# JETSON_V2.net
KiCad netlist of a schematic drawn in Altium Designer
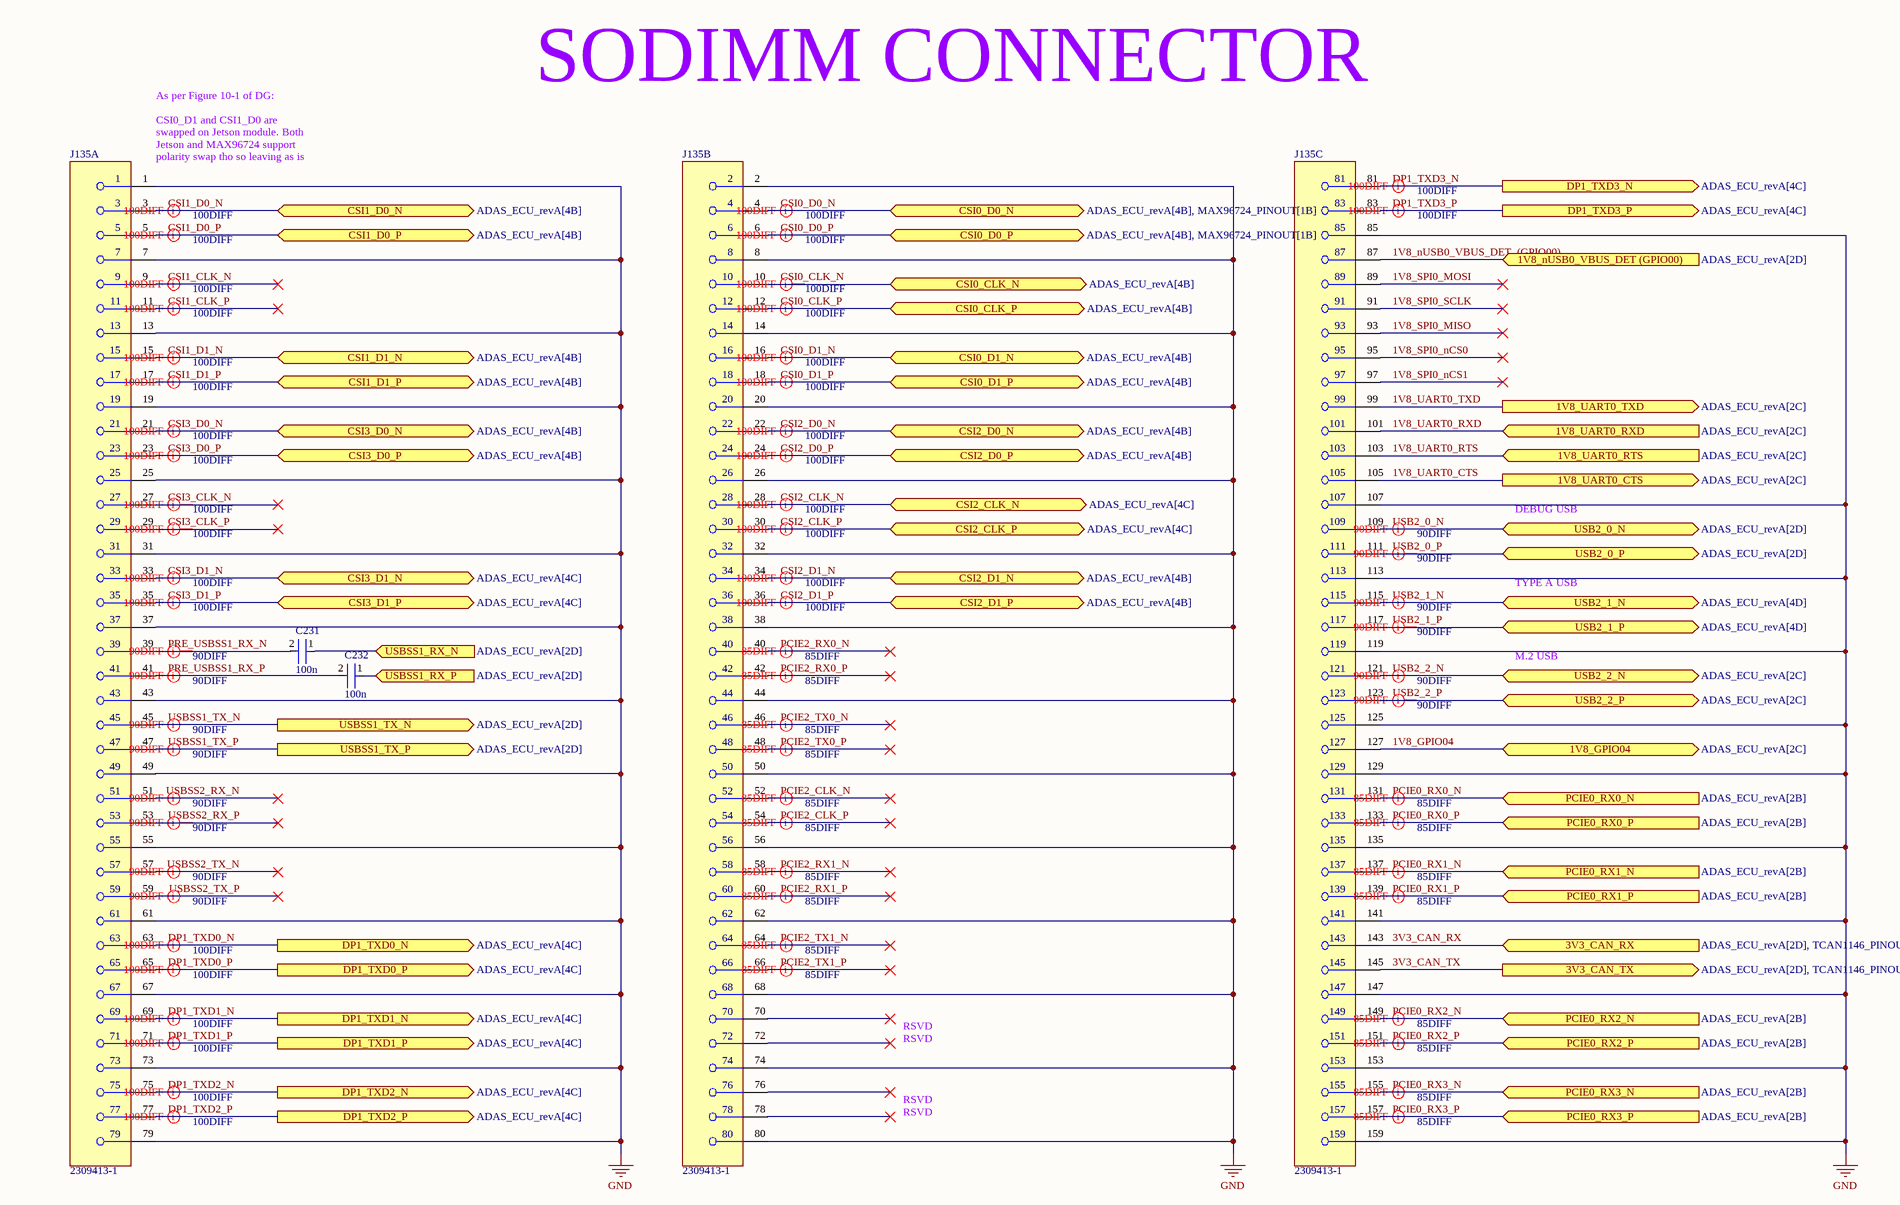
[diagram p0: JETSON_V2.SchDoc, top left]
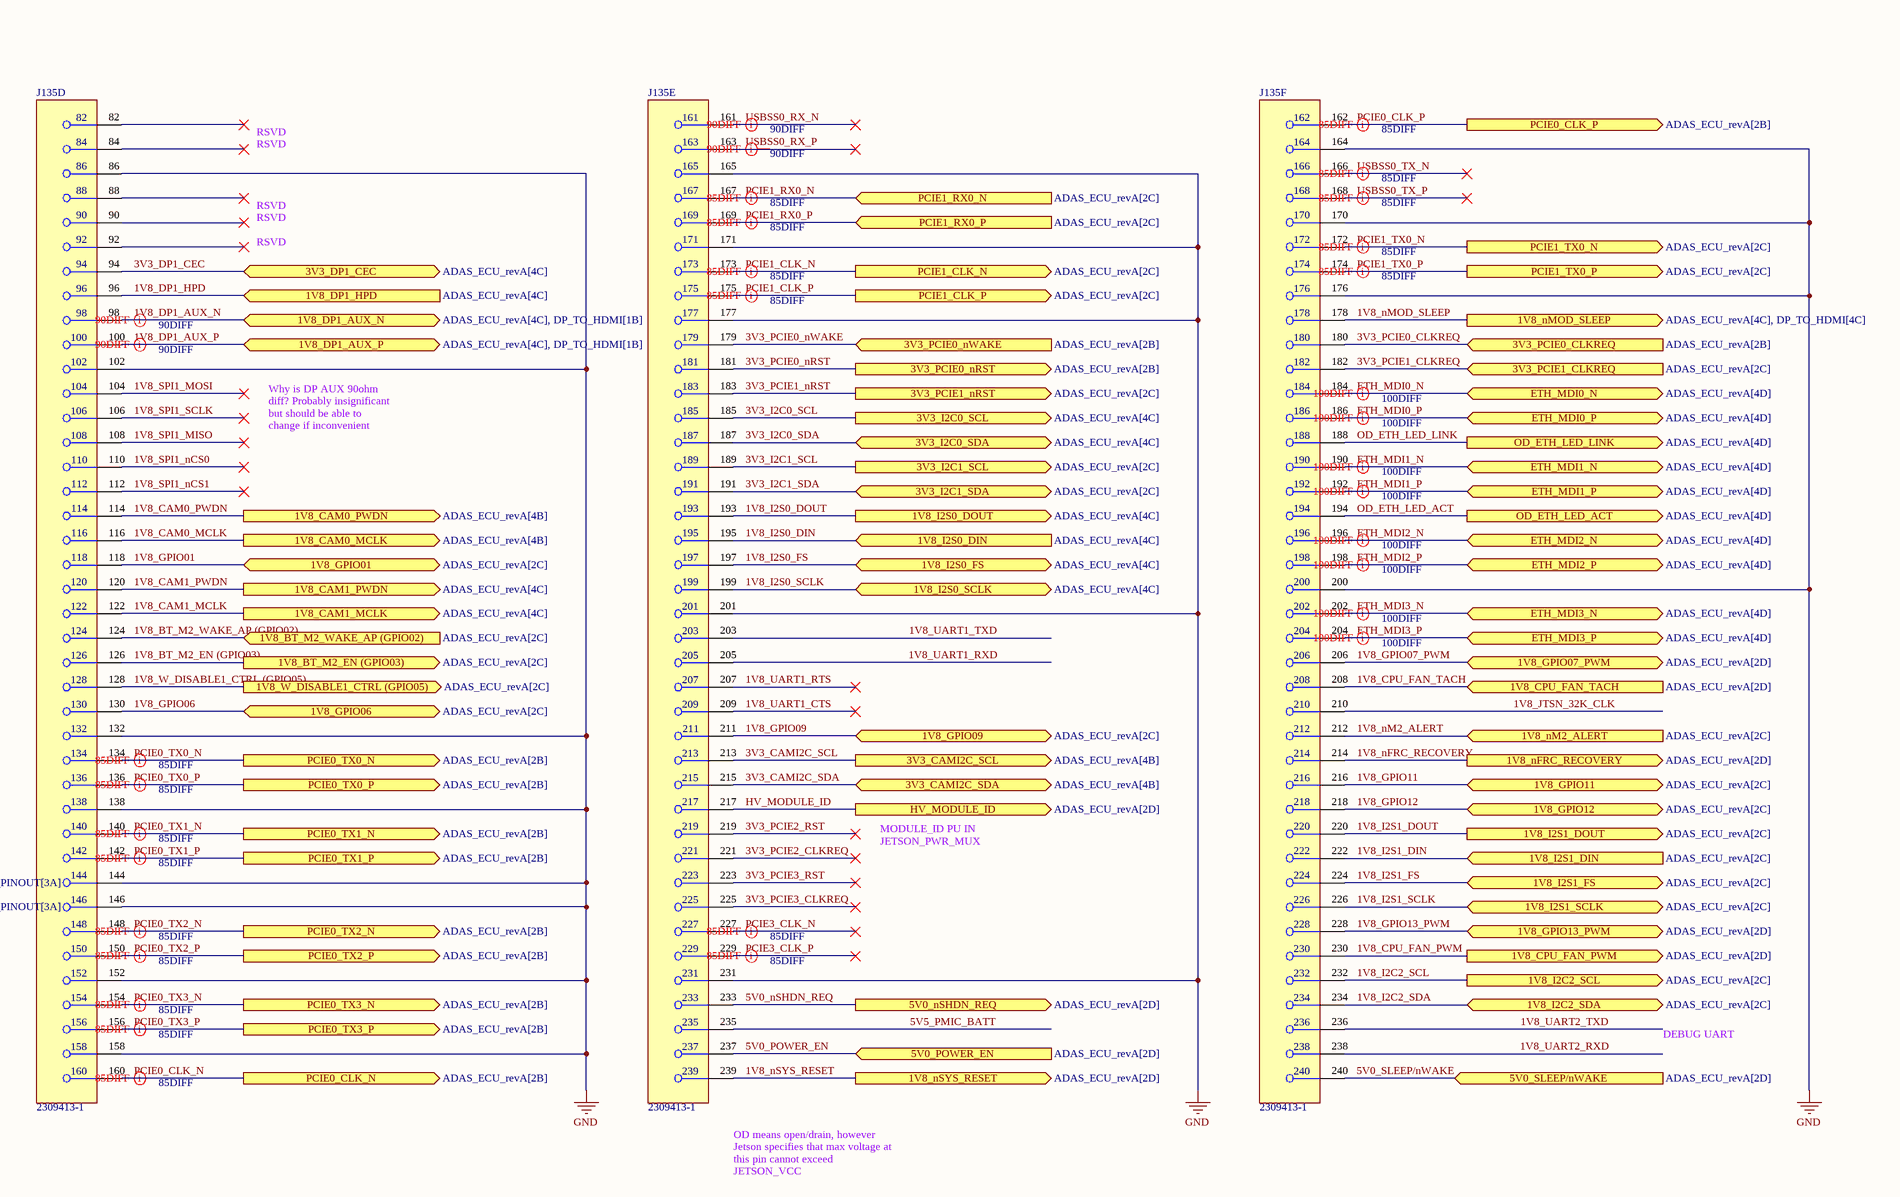
[diagram p1: JETSON_V2.SchDoc, top right]
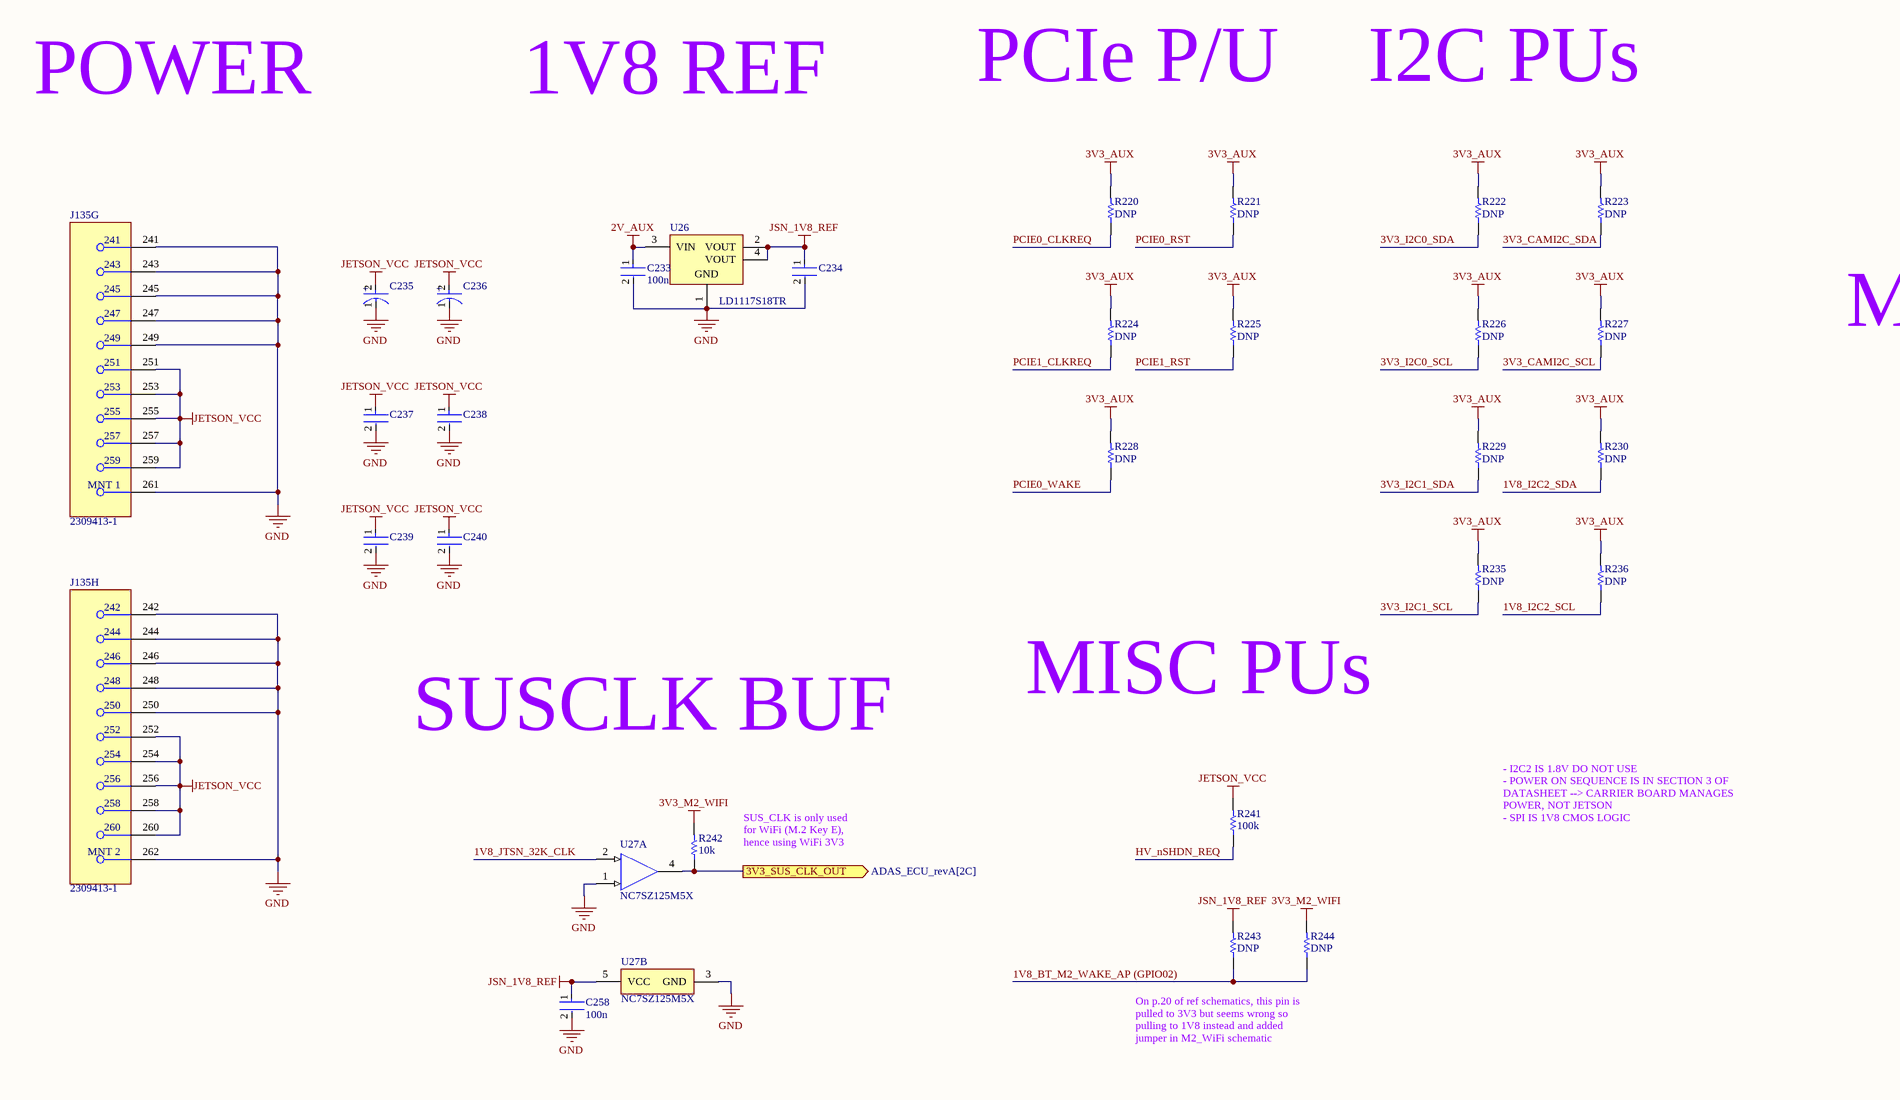
[diagram p2: JETSON_V2.SchDoc, bottom left]
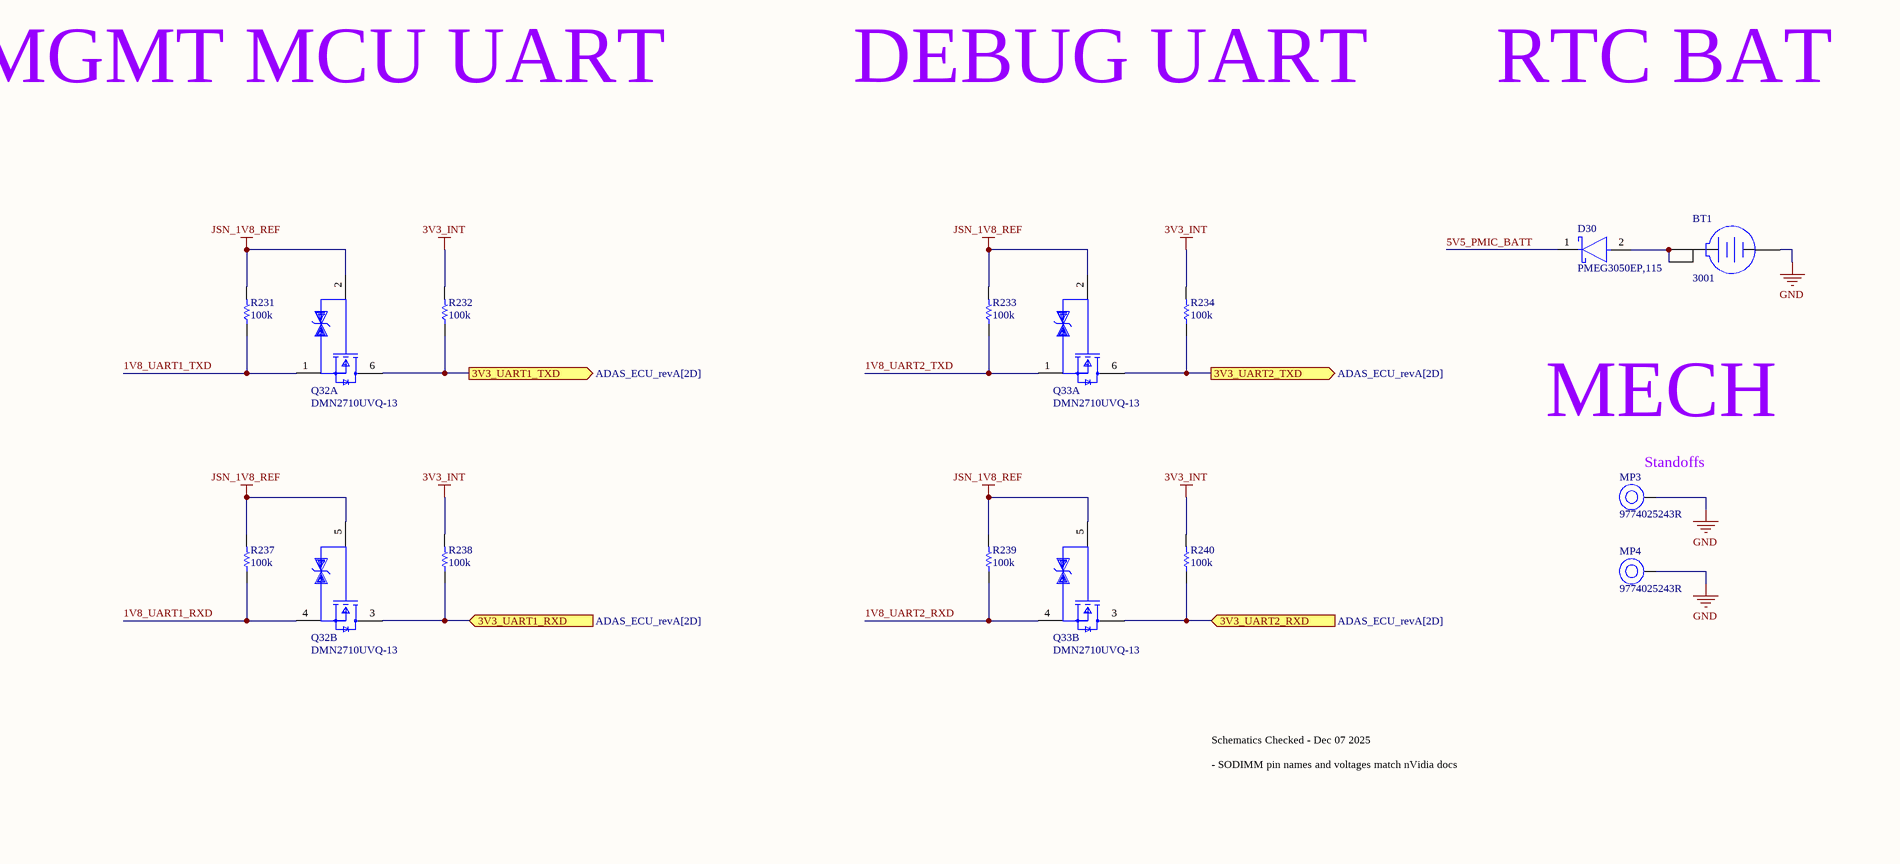
[diagram p3: JETSON_V2.SchDoc, bottom right]

(export (version "E")
  (design (tool "Eeschema 10.0.6"))
  (components
    (comp (ref "BT1")
      (value "3001")
      (footprint "KSTN-3001_V")
      (description "Holder Battery Coin, 12 mm, 2-Pin THD, RoHS")
      (fields (field (name "MANUFACTURER") "Keystone"))
      (libsource (lib "Altium Content Vault") (part "BATTERY-HOLDER-COIN-3"))
    )
    (comp (ref "C231")
      (value "100n")
      (footprint "FP-0402-L_1_0_0_05-W_0_5-IPC_A")
      (description "LARGE PADS, 0402 CAP, CHANGE COMMENT TO MATCH REAL P/N")
      (libsource (lib "Space Concordia") (part "b4654b650e69147ec39a6b967a45e02"))
    )
    (comp (ref "C232")
      (value "100n")
      (footprint "FP-0402-L_1_0_0_05-W_0_5-IPC_A")
      (description "LARGE PADS, 0402 CAP, CHANGE COMMENT TO MATCH REAL P/N")
      (libsource (lib "Space Concordia") (part "b4654b650e69147ec39a6b967a45e02"))
    )
    (comp (ref "C233")
      (value "100n")
      (footprint "FP-0402-L_1_0_0_05-W_0_5-IPC_A")
      (description "LARGE PADS, 0402 CAP, CHANGE COMMENT TO MATCH REAL P/N")
      (libsource (lib "Space Concordia") (part "b4654b650e69147ec39a6b967a45e02"))
    )
    (comp (ref "C234")
      (value "GRM188R60J106ME47D")
      (footprint "FP-GRM188-0_1-e0_2_0_55-IPC_A")
      (description "Chip Multilayer Ceramic Capacitors for General Purpose, 0603, 10uF, X5R, 15%, 20%, 6.3V")
      (fields (field (name "VOLTAGE") "6.3V") (field (name "TOLERANCE") "20%"))
      (libsource (lib "Altium Content Vault") (part "02cd4be3c70576c341d710602a673aa"))
    )
    (comp (ref "C235")
      (value "T491X107K025AT")
      (footprint "FP-T491X107K025AT-MFG")
      (description "CAP TANT 100UF 10% 25V 2917")
      (fields (field (name "TOLERANCE") "10%") (field (name "VOLTAGE") "25V"))
      (libsource (lib "Altium Content Vault") (part "cf48714ba7e38822c1575c7ec0b6d1f"))
    )
    (comp (ref "C236")
      (value "T491X107K025AT")
      (footprint "FP-T491X107K025AT-MFG")
      (description "CAP TANT 100UF 10% 25V 2917")
      (fields (field (name "TOLERANCE") "10%") (field (name "VOLTAGE") "25V"))
      (libsource (lib "Altium Content Vault") (part "cf48714ba7e38822c1575c7ec0b6d1f"))
    )
    (comp (ref "C237")
      (value "12103D106KAT2A")
      (footprint "FP-1210-L_3_3_0_4-W_2_5_0-MFG")
      (description "General Purpose Ceramic Capacitor, 1210, 10uF, 10%, X5R, 15%, 25V")
      (fields (field (name "VOLTAGE") "25V") (field (name "TOLERANCE") "10%"))
      (libsource (lib "Altium Content Vault") (part "b4654b650e69147ec39a6b967a45e02"))
    )
    (comp (ref "C238")
      (value "12103D106KAT2A")
      (footprint "FP-1210-L_3_3_0_4-W_2_5_0-MFG")
      (description "General Purpose Ceramic Capacitor, 1210, 10uF, 10%, X5R, 15%, 25V")
      (fields (field (name "VOLTAGE") "25V") (field (name "TOLERANCE") "10%"))
      (libsource (lib "Altium Content Vault") (part "b4654b650e69147ec39a6b967a45e02"))
    )
    (comp (ref "C239")
      (value "12103D106KAT2A")
      (footprint "FP-1210-L_3_3_0_4-W_2_5_0-MFG")
      (description "General Purpose Ceramic Capacitor, 1210, 10uF, 10%, X5R, 15%, 25V")
      (fields (field (name "VOLTAGE") "25V") (field (name "TOLERANCE") "10%"))
      (libsource (lib "Altium Content Vault") (part "b4654b650e69147ec39a6b967a45e02"))
    )
    (comp (ref "C240")
      (value "12103D106KAT2A")
      (footprint "FP-1210-L_3_3_0_4-W_2_5_0-MFG")
      (description "General Purpose Ceramic Capacitor, 1210, 10uF, 10%, X5R, 15%, 25V")
      (fields (field (name "VOLTAGE") "25V") (field (name "TOLERANCE") "10%"))
      (libsource (lib "Altium Content Vault") (part "b4654b650e69147ec39a6b967a45e02"))
    )
    (comp (ref "C258")
      (value "100n")
      (footprint "FP-0402-L_1_0_0_05-W_0_5-IPC_A")
      (description "LARGE PADS, 0402 CAP, CHANGE COMMENT TO MATCH REAL P/N")
      (libsource (lib "Space Concordia") (part "b4654b650e69147ec39a6b967a45e02"))
    )
    (comp (ref "D30")
      (value "PMEG3050EP,115")
      (footprint "FP-SOD128-MFG")
      (description "DIODE SCHOTTKY 30V 5A SOD128")
      (libsource (lib "Altium Content Vault") (part "1d6ec82d83fb6aee721767c19dac4b9"))
    )
    (comp (ref "J135")
      (value "2309413-1")
      (footprint "FP-2309413-1-MFG")
      (description "DDR4 SODIMM 260P 9.2H STD")
      (fields
        (field (name "OCTOPART") "https://octopart.com/2309413-1-te+connectivity-84799194")
        (field (name "MANUFACTURER") "TE Connectivity")
      )
      (libsource (lib "Altium Content Vault") (part "4d1075b24ee2591bdcd47d674b3d2aa"))
    )
    (comp (ref "MP3")
      (value "9774025243R")
      (footprint "9774025243")
      (description "9774025243R Spacer Material: Steel, Tin-Plated Mounting: SMT Series: WA-SMST Thread D: M2")
      (libsource (lib "Altium Content Vault") (part "Spacer"))
    )
    (comp (ref "MP4")
      (value "9774025243R")
      (footprint "9774025243")
      (description "9774025243R Spacer Material: Steel, Tin-Plated Mounting: SMT Series: WA-SMST Thread D: M2")
      (libsource (lib "Altium Content Vault") (part "Spacer"))
    )
    (comp (ref "Q32")
      (value "DMN2710UVQ-13")
      (footprint "SOTFL50P162X60-6N")
      (description "MOSFET Array, Dual N Channel, 20 V, 920 mA, 450 Milliohms, SOT-563, 6 Pins")
      (libsource (lib "Space Concordia") (part "DMN2710UVQ-13"))
    )
    (comp (ref "Q33")
      (value "DMN2710UVQ-13")
      (footprint "SOTFL50P162X60-6N")
      (description "MOSFET Array, Dual N Channel, 20 V, 920 mA, 450 Milliohms, SOT-563, 6 Pins")
      (libsource (lib "Space Concordia") (part "DMN2710UVQ-13"))
    )
    (comp (ref "R220")
      (value "DNP")
      (footprint "R0603B")
      (description "Resistor")
      (libsource (lib "Space Concordia") (part "Resistor"))
    )
    (comp (ref "R221")
      (value "DNP")
      (footprint "R0603B")
      (description "Resistor")
      (libsource (lib "Space Concordia") (part "Resistor"))
    )
    (comp (ref "R222")
      (value "DNP")
      (footprint "R0603B")
      (description "Resistor")
      (libsource (lib "Space Concordia") (part "Resistor"))
    )
    (comp (ref "R223")
      (value "DNP")
      (footprint "R0603B")
      (description "Resistor")
      (libsource (lib "Space Concordia") (part "Resistor"))
    )
    (comp (ref "R224")
      (value "DNP")
      (footprint "R0603B")
      (description "Resistor")
      (libsource (lib "Space Concordia") (part "Resistor"))
    )
    (comp (ref "R225")
      (value "DNP")
      (footprint "R0603B")
      (description "Resistor")
      (libsource (lib "Space Concordia") (part "Resistor"))
    )
    (comp (ref "R226")
      (value "DNP")
      (footprint "R0603B")
      (description "Resistor")
      (libsource (lib "Space Concordia") (part "Resistor"))
    )
    (comp (ref "R227")
      (value "DNP")
      (footprint "R0603B")
      (description "Resistor")
      (libsource (lib "Space Concordia") (part "Resistor"))
    )
    (comp (ref "R228")
      (value "DNP")
      (footprint "R0603B")
      (description "Resistor")
      (libsource (lib "Space Concordia") (part "Resistor"))
    )
    (comp (ref "R229")
      (value "DNP")
      (footprint "R0603B")
      (description "Resistor")
      (libsource (lib "Space Concordia") (part "Resistor"))
    )
    (comp (ref "R230")
      (value "DNP")
      (footprint "R0603B")
      (description "Resistor")
      (libsource (lib "Space Concordia") (part "Resistor"))
    )
    (comp (ref "R231")
      (value "100k")
      (footprint "R0603B")
      (description "Resistor")
      (libsource (lib "Space Concordia") (part "Resistor"))
    )
    (comp (ref "R232")
      (value "100k")
      (footprint "R0603B")
      (description "Resistor")
      (libsource (lib "Space Concordia") (part "Resistor"))
    )
    (comp (ref "R233")
      (value "100k")
      (footprint "R0603B")
      (description "Resistor")
      (libsource (lib "Space Concordia") (part "Resistor"))
    )
    (comp (ref "R234")
      (value "100k")
      (footprint "R0603B")
      (description "Resistor")
      (libsource (lib "Space Concordia") (part "Resistor"))
    )
    (comp (ref "R235")
      (value "DNP")
      (footprint "R0603B")
      (description "Resistor")
      (libsource (lib "Space Concordia") (part "Resistor"))
    )
    (comp (ref "R236")
      (value "DNP")
      (footprint "R0603B")
      (description "Resistor")
      (libsource (lib "Space Concordia") (part "Resistor"))
    )
    (comp (ref "R237")
      (value "100k")
      (footprint "R0603B")
      (description "Resistor")
      (libsource (lib "Space Concordia") (part "Resistor"))
    )
    (comp (ref "R238")
      (value "100k")
      (footprint "R0603B")
      (description "Resistor")
      (libsource (lib "Space Concordia") (part "Resistor"))
    )
    (comp (ref "R239")
      (value "100k")
      (footprint "R0603B")
      (description "Resistor")
      (libsource (lib "Space Concordia") (part "Resistor"))
    )
    (comp (ref "R240")
      (value "100k")
      (footprint "R0603B")
      (description "Resistor")
      (libsource (lib "Space Concordia") (part "Resistor"))
    )
    (comp (ref "R241")
      (value "100k")
      (footprint "R0603B")
      (description "Resistor")
      (libsource (lib "Space Concordia") (part "Resistor"))
    )
    (comp (ref "R242")
      (value "10k")
      (footprint "R0603B")
      (description "Resistor")
      (libsource (lib "Space Concordia") (part "Resistor"))
    )
    (comp (ref "R243")
      (value "DNP")
      (footprint "R0603B")
      (description "Resistor")
      (libsource (lib "Space Concordia") (part "Resistor"))
    )
    (comp (ref "R244")
      (value "DNP")
      (footprint "R0603B")
      (description "Resistor")
      (libsource (lib "Space Concordia") (part "Resistor"))
    )
    (comp (ref "U26")
      (value "LD1117S18TR")
      (footprint "SOT-223_M")
      (description "Fixed Low Drop Positive Voltage Regulator, 1.8V, 4-Pin SOT-223, Tape and Reel")
      (libsource (lib "Altium Content Vault") (part "PM-REG-LD1117-SOT4"))
    )
    (comp (ref "U27")
      (value "NC7SZ125M5X")
      (footprint "FAIR-SOT23-5_V")
      (fields (field (name "MANUFACTURER") "Fairchild Semiconductor"))
      (libsource (lib "") (part "FAIR-NC7SZ125-SOT23-5_1"))
    )
  )
  (nets
    (net (code "1") (name "/1V8_BT_M2_EN (GPIO03)") (class "Default")
      (node (ref "J135") (pin "126") (pinfunction "126_126") (pintype "passive"))
    )
    (net (code "2") (name "/1V8_BT_M2_WAKE_AP (GPIO02)") (class "Default")
      (node (ref "J135") (pin "124") (pinfunction "124_124") (pintype "passive"))
      (node (ref "R243") (pin "1") (pinfunction "1_1") (pintype "passive"))
      (node (ref "R244") (pin "1") (pinfunction "1_1") (pintype "passive"))
    )
    (net (code "3") (name "/1V8_CAM0_MCLK") (class "Default")
      (node (ref "J135") (pin "116") (pinfunction "116_116") (pintype "passive"))
    )
    (net (code "4") (name "/1V8_CAM0_PWDN") (class "Default")
      (node (ref "J135") (pin "114") (pinfunction "114_114") (pintype "passive"))
    )
    (net (code "5") (name "/1V8_CAM1_MCLK") (class "Default")
      (node (ref "J135") (pin "122") (pinfunction "122_122") (pintype "passive"))
    )
    (net (code "6") (name "/1V8_CAM1_PWDN") (class "Default")
      (node (ref "J135") (pin "120") (pinfunction "120_120") (pintype "passive"))
    )
    (net (code "7") (name "/1V8_CPU_FAN_PWM") (class "Default")
      (node (ref "J135") (pin "230") (pinfunction "230_230") (pintype "passive"))
    )
    (net (code "8") (name "/1V8_CPU_FAN_TACH") (class "Default")
      (node (ref "J135") (pin "208") (pinfunction "208_208") (pintype "passive"))
    )
    (net (code "9") (name "/1V8_DP1_AUX_N") (class "Default")
      (node (ref "J135") (pin "98") (pinfunction "98_98") (pintype "passive"))
    )
    (net (code "10") (name "/1V8_DP1_AUX_P") (class "Default")
      (node (ref "J135") (pin "100") (pinfunction "100_100") (pintype "passive"))
    )
    (net (code "11") (name "/1V8_DP1_HPD") (class "Default")
      (node (ref "J135") (pin "96") (pinfunction "96_96") (pintype "passive"))
    )
    (net (code "12") (name "/1V8_GPIO01") (class "Default")
      (node (ref "J135") (pin "118") (pinfunction "118_118") (pintype "passive"))
    )
    (net (code "13") (name "/1V8_GPIO04") (class "Default")
      (node (ref "J135") (pin "127") (pinfunction "127_127") (pintype "passive"))
    )
    (net (code "14") (name "/1V8_GPIO06") (class "Default")
      (node (ref "J135") (pin "130") (pinfunction "130_130") (pintype "passive"))
    )
    (net (code "15") (name "/1V8_GPIO07_PWM") (class "Default")
      (node (ref "J135") (pin "206") (pinfunction "206_206") (pintype "passive"))
    )
    (net (code "16") (name "/1V8_GPIO09") (class "Default")
      (node (ref "J135") (pin "211") (pinfunction "211_211") (pintype "passive"))
    )
    (net (code "17") (name "/1V8_GPIO11") (class "Default")
      (node (ref "J135") (pin "216") (pinfunction "216_216") (pintype "passive"))
    )
    (net (code "18") (name "/1V8_GPIO12") (class "Default")
      (node (ref "J135") (pin "218") (pinfunction "218_218") (pintype "passive"))
    )
    (net (code "19") (name "/1V8_GPIO13_PWM") (class "Default")
      (node (ref "J135") (pin "228") (pinfunction "228_228") (pintype "passive"))
    )
    (net (code "20") (name "/1V8_I2C2_SCL") (class "Default")
      (node (ref "J135") (pin "232") (pinfunction "232_232") (pintype "passive"))
      (node (ref "R236") (pin "1") (pinfunction "1_1") (pintype "passive"))
    )
    (net (code "21") (name "/1V8_I2C2_SDA") (class "Default")
      (node (ref "J135") (pin "234") (pinfunction "234_234") (pintype "passive"))
      (node (ref "R230") (pin "1") (pinfunction "1_1") (pintype "passive"))
    )
    (net (code "22") (name "/1V8_I2S0_DIN") (class "Default")
      (node (ref "J135") (pin "195") (pinfunction "195_195") (pintype "passive"))
    )
    (net (code "23") (name "/1V8_I2S0_DOUT") (class "Default")
      (node (ref "J135") (pin "193") (pinfunction "193_193") (pintype "passive"))
    )
    (net (code "24") (name "/1V8_I2S0_FS") (class "Default")
      (node (ref "J135") (pin "197") (pinfunction "197_197") (pintype "passive"))
    )
    (net (code "25") (name "/1V8_I2S0_SCLK") (class "Default")
      (node (ref "J135") (pin "199") (pinfunction "199_199") (pintype "passive"))
    )
    (net (code "26") (name "/1V8_I2S1_DIN") (class "Default")
      (node (ref "J135") (pin "222") (pinfunction "222_222") (pintype "passive"))
    )
    (net (code "27") (name "/1V8_I2S1_DOUT") (class "Default")
      (node (ref "J135") (pin "220") (pinfunction "220_220") (pintype "passive"))
    )
    (net (code "28") (name "/1V8_I2S1_FS") (class "Default")
      (node (ref "J135") (pin "224") (pinfunction "224_224") (pintype "passive"))
    )
    (net (code "29") (name "/1V8_I2S1_SCLK") (class "Default")
      (node (ref "J135") (pin "226") (pinfunction "226_226") (pintype "passive"))
    )
    (net (code "30") (name "/1V8_JTSN_32K_CLK") (class "Default")
      (node (ref "J135") (pin "210") (pinfunction "210_210") (pintype "passive"))
      (node (ref "U27") (pin "2") (pinfunction "A_2") (pintype "input"))
    )
    (net (code "31") (name "/1V8_SPI0_MISO") (class "Default")
      (node (ref "J135") (pin "93") (pinfunction "93_93") (pintype "passive+no_connect"))
    )
    (net (code "32") (name "/1V8_SPI0_MOSI") (class "Default")
      (node (ref "J135") (pin "89") (pinfunction "89_89") (pintype "passive+no_connect"))
    )
    (net (code "33") (name "/1V8_SPI0_SCLK") (class "Default")
      (node (ref "J135") (pin "91") (pinfunction "91_91") (pintype "passive+no_connect"))
    )
    (net (code "34") (name "/1V8_SPI0_nCS0") (class "Default")
      (node (ref "J135") (pin "95") (pinfunction "95_95") (pintype "passive+no_connect"))
    )
    (net (code "35") (name "/1V8_SPI0_nCS1") (class "Default")
      (node (ref "J135") (pin "97") (pinfunction "97_97") (pintype "passive+no_connect"))
    )
    (net (code "36") (name "/1V8_SPI1_MISO") (class "Default")
      (node (ref "J135") (pin "108") (pinfunction "108_108") (pintype "passive+no_connect"))
    )
    (net (code "37") (name "/1V8_SPI1_MOSI") (class "Default")
      (node (ref "J135") (pin "104") (pinfunction "104_104") (pintype "passive+no_connect"))
    )
    (net (code "38") (name "/1V8_SPI1_SCLK") (class "Default")
      (node (ref "J135") (pin "106") (pinfunction "106_106") (pintype "passive+no_connect"))
    )
    (net (code "39") (name "/1V8_SPI1_nCS0") (class "Default")
      (node (ref "J135") (pin "110") (pinfunction "110_110") (pintype "passive+no_connect"))
    )
    (net (code "40") (name "/1V8_SPI1_nCS1") (class "Default")
      (node (ref "J135") (pin "112") (pinfunction "112_112") (pintype "passive+no_connect"))
    )
    (net (code "41") (name "/1V8_UART0_CTS") (class "Default")
      (node (ref "J135") (pin "105") (pinfunction "105_105") (pintype "passive"))
    )
    (net (code "42") (name "/1V8_UART0_RTS") (class "Default")
      (node (ref "J135") (pin "103") (pinfunction "103_103") (pintype "passive"))
    )
    (net (code "43") (name "/1V8_UART0_RXD") (class "Default")
      (node (ref "J135") (pin "101") (pinfunction "101_101") (pintype "passive"))
    )
    (net (code "44") (name "/1V8_UART0_TXD") (class "Default")
      (node (ref "J135") (pin "99") (pinfunction "99_99") (pintype "passive"))
    )
    (net (code "45") (name "/1V8_UART1_CTS") (class "Default")
      (node (ref "J135") (pin "209") (pinfunction "209_209") (pintype "passive+no_connect"))
    )
    (net (code "46") (name "/1V8_UART1_RTS") (class "Default")
      (node (ref "J135") (pin "207") (pinfunction "207_207") (pintype "passive+no_connect"))
    )
    (net (code "47") (name "/1V8_UART1_RXD") (class "Default")
      (node (ref "J135") (pin "205") (pinfunction "205_205") (pintype "passive"))
      (node (ref "Q32") (pin "4") (pinfunction "Source2_4") (pintype "passive"))
      (node (ref "R237") (pin "1") (pinfunction "1_1") (pintype "passive"))
    )
    (net (code "48") (name "/1V8_UART1_TXD") (class "Default")
      (node (ref "J135") (pin "203") (pinfunction "203_203") (pintype "passive"))
      (node (ref "Q32") (pin "1") (pinfunction "Source1_1") (pintype "passive"))
      (node (ref "R231") (pin "1") (pinfunction "1_1") (pintype "passive"))
    )
    (net (code "49") (name "/1V8_UART2_RXD") (class "Default")
      (node (ref "J135") (pin "238") (pinfunction "238_238") (pintype "passive"))
      (node (ref "Q33") (pin "4") (pinfunction "Source2_4") (pintype "passive"))
      (node (ref "R239") (pin "1") (pinfunction "1_1") (pintype "passive"))
    )
    (net (code "50") (name "/1V8_UART2_TXD") (class "Default")
      (node (ref "J135") (pin "236") (pinfunction "236_236") (pintype "passive"))
      (node (ref "Q33") (pin "1") (pinfunction "Source1_1") (pintype "passive"))
      (node (ref "R233") (pin "1") (pinfunction "1_1") (pintype "passive"))
    )
    (net (code "51") (name "/1V8_W_DISABLE1_CTRL (GPIO05)") (class "Default")
      (node (ref "J135") (pin "128") (pinfunction "128_128") (pintype "passive"))
    )
    (net (code "52") (name "/1V8_nFRC_RECOVERY") (class "Default")
      (node (ref "J135") (pin "214") (pinfunction "214_214") (pintype "passive"))
    )
    (net (code "53") (name "/1V8_nM2_ALERT") (class "Default")
      (node (ref "J135") (pin "212") (pinfunction "212_212") (pintype "passive"))
    )
    (net (code "54") (name "/1V8_nMOD_SLEEP") (class "Default")
      (node (ref "J135") (pin "178") (pinfunction "178_178") (pintype "passive"))
    )
    (net (code "55") (name "/1V8_nSYS_RESET") (class "Default")
      (node (ref "J135") (pin "239") (pinfunction "239_239") (pintype "passive"))
    )
    (net (code "56") (name "/1V8_nUSB0_VBUS_DET  (GPIO00)") (class "Default")
      (node (ref "J135") (pin "87") (pinfunction "87_87") (pintype "passive"))
    )
    (net (code "57") (name "/3V3_CAMI2C_SCL") (class "Default")
      (node (ref "J135") (pin "213") (pinfunction "213_213") (pintype "passive"))
      (node (ref "R227") (pin "1") (pinfunction "1_1") (pintype "passive"))
    )
    (net (code "58") (name "/3V3_CAMI2C_SDA") (class "Default")
      (node (ref "J135") (pin "215") (pinfunction "215_215") (pintype "passive"))
      (node (ref "R223") (pin "1") (pinfunction "1_1") (pintype "passive"))
    )
    (net (code "59") (name "/3V3_CAN_RX") (class "Default")
      (node (ref "J135") (pin "143") (pinfunction "143_143") (pintype "passive"))
    )
    (net (code "60") (name "/3V3_CAN_TX") (class "Default")
      (node (ref "J135") (pin "145") (pinfunction "145_145") (pintype "passive"))
    )
    (net (code "61") (name "/3V3_DP1_CEC") (class "Default")
      (node (ref "J135") (pin "94") (pinfunction "94_94") (pintype "passive"))
    )
    (net (code "62") (name "/3V3_I2C0_SCL") (class "Default")
      (node (ref "J135") (pin "185") (pinfunction "185_185") (pintype "passive"))
      (node (ref "R226") (pin "1") (pinfunction "1_1") (pintype "passive"))
    )
    (net (code "63") (name "/3V3_I2C0_SDA") (class "Default")
      (node (ref "J135") (pin "187") (pinfunction "187_187") (pintype "passive"))
      (node (ref "R222") (pin "1") (pinfunction "1_1") (pintype "passive"))
    )
    (net (code "64") (name "/3V3_I2C1_SCL") (class "Default")
      (node (ref "J135") (pin "189") (pinfunction "189_189") (pintype "passive"))
      (node (ref "R235") (pin "1") (pinfunction "1_1") (pintype "passive"))
    )
    (net (code "65") (name "/3V3_I2C1_SDA") (class "Default")
      (node (ref "J135") (pin "191") (pinfunction "191_191") (pintype "passive"))
      (node (ref "R229") (pin "1") (pinfunction "1_1") (pintype "passive"))
    )
    (net (code "66") (name "/3V3_PCIE0_CLKREQ") (class "Default")
      (node (ref "J135") (pin "180") (pinfunction "180_180") (pintype "passive"))
    )
    (net (code "67") (name "/3V3_PCIE0_nRST") (class "Default")
      (node (ref "J135") (pin "181") (pinfunction "181_181") (pintype "passive"))
    )
    (net (code "68") (name "/3V3_PCIE0_nWAKE") (class "Default")
      (node (ref "J135") (pin "179") (pinfunction "179_179") (pintype "passive"))
    )
    (net (code "69") (name "/3V3_PCIE1_CLKREQ") (class "Default")
      (node (ref "J135") (pin "182") (pinfunction "182_182") (pintype "passive"))
    )
    (net (code "70") (name "/3V3_PCIE1_nRST") (class "Default")
      (node (ref "J135") (pin "183") (pinfunction "183_183") (pintype "passive"))
    )
    (net (code "71") (name "/3V3_PCIE2_CLKREQ") (class "Default")
      (node (ref "J135") (pin "221") (pinfunction "221_221") (pintype "passive+no_connect"))
    )
    (net (code "72") (name "/3V3_PCIE2_RST") (class "Default")
      (node (ref "J135") (pin "219") (pinfunction "219_219") (pintype "passive+no_connect"))
    )
    (net (code "73") (name "/3V3_PCIE3_CLKREQ") (class "Default")
      (node (ref "J135") (pin "225") (pinfunction "225_225") (pintype "passive+no_connect"))
    )
    (net (code "74") (name "/3V3_PCIE3_RST") (class "Default")
      (node (ref "J135") (pin "223") (pinfunction "223_223") (pintype "passive+no_connect"))
    )
    (net (code "75") (name "/3V3_SUS_CLK_OUT") (class "Default")
      (node (ref "R242") (pin "1") (pinfunction "1_1") (pintype "passive"))
      (node (ref "U27") (pin "4") (pinfunction "Y_4") (pintype "tri_state"))
    )
    (net (code "76") (name "/3V3_UART1_RXD") (class "Default")
      (node (ref "Q32") (pin "3") (pinfunction "Drain2_3") (pintype "passive"))
      (node (ref "R238") (pin "1") (pinfunction "1_1") (pintype "passive"))
    )
    (net (code "77") (name "/3V3_UART1_TXD") (class "Default")
      (node (ref "Q32") (pin "6") (pinfunction "Drain1_6") (pintype "passive"))
      (node (ref "R232") (pin "1") (pinfunction "1_1") (pintype "passive"))
    )
    (net (code "78") (name "/3V3_UART2_RXD") (class "Default")
      (node (ref "Q33") (pin "3") (pinfunction "Drain2_3") (pintype "passive"))
      (node (ref "R240") (pin "1") (pinfunction "1_1") (pintype "passive"))
    )
    (net (code "79") (name "/3V3_UART2_TXD") (class "Default")
      (node (ref "Q33") (pin "6") (pinfunction "Drain1_6") (pintype "passive"))
      (node (ref "R234") (pin "1") (pinfunction "1_1") (pintype "passive"))
    )
    (net (code "80") (name "/5V0_POWER_EN") (class "Default")
      (node (ref "J135") (pin "237") (pinfunction "237_237") (pintype "passive"))
    )
    (net (code "81") (name "/5V0_SLEEP{slash}nWAKE") (class "Default")
      (node (ref "J135") (pin "240") (pinfunction "240_240") (pintype "passive"))
    )
    (net (code "82") (name "/5V0_nSHDN_REQ") (class "Default")
      (node (ref "J135") (pin "233") (pinfunction "233_233") (pintype "passive"))
    )
    (net (code "83") (name "/5V5_PMIC_BATT") (class "Default")
      (node (ref "D30") (pin "1") (pinfunction "C_1") (pintype "passive"))
      (node (ref "J135") (pin "235") (pinfunction "235_235") (pintype "passive"))
    )
    (net (code "84") (name "/CSI0_CLK_N") (class "Default")
      (node (ref "J135") (pin "10") (pinfunction "10_10") (pintype "passive"))
    )
    (net (code "85") (name "/CSI0_CLK_P") (class "Default")
      (node (ref "J135") (pin "12") (pinfunction "12_12") (pintype "passive"))
    )
    (net (code "86") (name "/CSI0_D0_N") (class "Default")
      (node (ref "J135") (pin "4") (pinfunction "4_4") (pintype "passive"))
    )
    (net (code "87") (name "/CSI0_D0_P") (class "Default")
      (node (ref "J135") (pin "6") (pinfunction "6_6") (pintype "passive"))
    )
    (net (code "88") (name "/CSI0_D1_N") (class "Default")
      (node (ref "J135") (pin "16") (pinfunction "16_16") (pintype "passive"))
    )
    (net (code "89") (name "/CSI0_D1_P") (class "Default")
      (node (ref "J135") (pin "18") (pinfunction "18_18") (pintype "passive"))
    )
    (net (code "90") (name "/CSI1_CLK_N") (class "Default")
      (node (ref "J135") (pin "9") (pinfunction "9_9") (pintype "passive+no_connect"))
    )
    (net (code "91") (name "/CSI1_CLK_P") (class "Default")
      (node (ref "J135") (pin "11") (pinfunction "11_11") (pintype "passive+no_connect"))
    )
    (net (code "92") (name "/CSI1_D0_N") (class "Default")
      (node (ref "J135") (pin "3") (pinfunction "3_3") (pintype "passive"))
    )
    (net (code "93") (name "/CSI1_D0_P") (class "Default")
      (node (ref "J135") (pin "5") (pinfunction "5_5") (pintype "passive"))
    )
    (net (code "94") (name "/CSI1_D1_N") (class "Default")
      (node (ref "J135") (pin "15") (pinfunction "15_15") (pintype "passive"))
    )
    (net (code "95") (name "/CSI1_D1_P") (class "Default")
      (node (ref "J135") (pin "17") (pinfunction "17_17") (pintype "passive"))
    )
    (net (code "96") (name "/CSI2_CLK_N") (class "Default")
      (node (ref "J135") (pin "28") (pinfunction "28_28") (pintype "passive"))
    )
    (net (code "97") (name "/CSI2_CLK_P") (class "Default")
      (node (ref "J135") (pin "30") (pinfunction "30_30") (pintype "passive"))
    )
    (net (code "98") (name "/CSI2_D0_N") (class "Default")
      (node (ref "J135") (pin "22") (pinfunction "22_22") (pintype "passive"))
    )
    (net (code "99") (name "/CSI2_D0_P") (class "Default")
      (node (ref "J135") (pin "24") (pinfunction "24_24") (pintype "passive"))
    )
    (net (code "100") (name "/CSI2_D1_N") (class "Default")
      (node (ref "J135") (pin "34") (pinfunction "34_34") (pintype "passive"))
    )
    (net (code "101") (name "/CSI2_D1_P") (class "Default")
      (node (ref "J135") (pin "36") (pinfunction "36_36") (pintype "passive"))
    )
    (net (code "102") (name "/CSI3_CLK_N") (class "Default")
      (node (ref "J135") (pin "27") (pinfunction "27_27") (pintype "passive+no_connect"))
    )
    (net (code "103") (name "/CSI3_CLK_P") (class "Default")
      (node (ref "J135") (pin "29") (pinfunction "29_29") (pintype "passive+no_connect"))
    )
    (net (code "104") (name "/CSI3_D0_N") (class "Default")
      (node (ref "J135") (pin "21") (pinfunction "21_21") (pintype "passive"))
    )
    (net (code "105") (name "/CSI3_D0_P") (class "Default")
      (node (ref "J135") (pin "23") (pinfunction "23_23") (pintype "passive"))
    )
    (net (code "106") (name "/CSI3_D1_N") (class "Default")
      (node (ref "J135") (pin "33") (pinfunction "33_33") (pintype "passive"))
    )
    (net (code "107") (name "/CSI3_D1_P") (class "Default")
      (node (ref "J135") (pin "35") (pinfunction "35_35") (pintype "passive"))
    )
    (net (code "108") (name "/DP1_TXD0_N") (class "Default")
      (node (ref "J135") (pin "63") (pinfunction "63_63") (pintype "passive"))
    )
    (net (code "109") (name "/DP1_TXD0_P") (class "Default")
      (node (ref "J135") (pin "65") (pinfunction "65_65") (pintype "passive"))
    )
    (net (code "110") (name "/DP1_TXD1_N") (class "Default")
      (node (ref "J135") (pin "69") (pinfunction "69_69") (pintype "passive"))
    )
    (net (code "111") (name "/DP1_TXD1_P") (class "Default")
      (node (ref "J135") (pin "71") (pinfunction "71_71") (pintype "passive"))
    )
    (net (code "112") (name "/DP1_TXD2_N") (class "Default")
      (node (ref "J135") (pin "75") (pinfunction "75_75") (pintype "passive"))
    )
    (net (code "113") (name "/DP1_TXD2_P") (class "Default")
      (node (ref "J135") (pin "77") (pinfunction "77_77") (pintype "passive"))
    )
    (net (code "114") (name "/DP1_TXD3_N") (class "Default")
      (node (ref "J135") (pin "81") (pinfunction "81_81") (pintype "passive"))
    )
    (net (code "115") (name "/DP1_TXD3_P") (class "Default")
      (node (ref "J135") (pin "83") (pinfunction "83_83") (pintype "passive"))
    )
    (net (code "116") (name "/ETH_MDI0_N") (class "Default")
      (node (ref "J135") (pin "184") (pinfunction "184_184") (pintype "passive"))
    )
    (net (code "117") (name "/ETH_MDI0_P") (class "Default")
      (node (ref "J135") (pin "186") (pinfunction "186_186") (pintype "passive"))
    )
    (net (code "118") (name "/ETH_MDI1_N") (class "Default")
      (node (ref "J135") (pin "190") (pinfunction "190_190") (pintype "passive"))
    )
    (net (code "119") (name "/ETH_MDI1_P") (class "Default")
      (node (ref "J135") (pin "192") (pinfunction "192_192") (pintype "passive"))
    )
    (net (code "120") (name "/ETH_MDI2_N") (class "Default")
      (node (ref "J135") (pin "196") (pinfunction "196_196") (pintype "passive"))
    )
    (net (code "121") (name "/ETH_MDI2_P") (class "Default")
      (node (ref "J135") (pin "198") (pinfunction "198_198") (pintype "passive"))
    )
    (net (code "122") (name "/ETH_MDI3_N") (class "Default")
      (node (ref "J135") (pin "202") (pinfunction "202_202") (pintype "passive"))
    )
    (net (code "123") (name "/ETH_MDI3_P") (class "Default")
      (node (ref "J135") (pin "204") (pinfunction "204_204") (pintype "passive"))
    )
    (net (code "124") (name "/HV_MODULE_ID") (class "Default")
      (node (ref "J135") (pin "217") (pinfunction "217_217") (pintype "passive"))
    )
    (net (code "125") (name "/HV_nSHDN_REQ") (class "Default")
      (node (ref "R241") (pin "1") (pinfunction "1_1") (pintype "passive"))
    )
    (net (code "126") (name "/OD_ETH_LED_ACT") (class "Default")
      (node (ref "J135") (pin "194") (pinfunction "194_194") (pintype "passive"))
    )
    (net (code "127") (name "/OD_ETH_LED_LINK") (class "Default")
      (node (ref "J135") (pin "188") (pinfunction "188_188") (pintype "passive"))
    )
    (net (code "128") (name "/PCIE0_CLKREQ") (class "Default")
      (node (ref "R220") (pin "1") (pinfunction "1_1") (pintype "passive"))
    )
    (net (code "129") (name "/PCIE0_CLK_N") (class "Default")
      (node (ref "J135") (pin "160") (pinfunction "160_160") (pintype "passive"))
    )
    (net (code "130") (name "/PCIE0_CLK_P") (class "Default")
      (node (ref "J135") (pin "162") (pinfunction "162_162") (pintype "passive"))
    )
    (net (code "131") (name "/PCIE0_RST") (class "Default")
      (node (ref "R221") (pin "1") (pinfunction "1_1") (pintype "passive"))
    )
    (net (code "132") (name "/PCIE0_RX0_N") (class "Default")
      (node (ref "J135") (pin "131") (pinfunction "131_131") (pintype "passive"))
    )
    (net (code "133") (name "/PCIE0_RX0_P") (class "Default")
      (node (ref "J135") (pin "133") (pinfunction "133_133") (pintype "passive"))
    )
    (net (code "134") (name "/PCIE0_RX1_N") (class "Default")
      (node (ref "J135") (pin "137") (pinfunction "137_137") (pintype "passive"))
    )
    (net (code "135") (name "/PCIE0_RX1_P") (class "Default")
      (node (ref "J135") (pin "139") (pinfunction "139_139") (pintype "passive"))
    )
    (net (code "136") (name "/PCIE0_RX2_N") (class "Default")
      (node (ref "J135") (pin "149") (pinfunction "149_149") (pintype "passive"))
    )
    (net (code "137") (name "/PCIE0_RX2_P") (class "Default")
      (node (ref "J135") (pin "151") (pinfunction "151_151") (pintype "passive"))
    )
    (net (code "138") (name "/PCIE0_RX3_N") (class "Default")
      (node (ref "J135") (pin "155") (pinfunction "155_155") (pintype "passive"))
    )
    (net (code "139") (name "/PCIE0_RX3_P") (class "Default")
      (node (ref "J135") (pin "157") (pinfunction "157_157") (pintype "passive"))
    )
    (net (code "140") (name "/PCIE0_TX0_N") (class "Default")
      (node (ref "J135") (pin "134") (pinfunction "134_134") (pintype "passive"))
    )
    (net (code "141") (name "/PCIE0_TX0_P") (class "Default")
      (node (ref "J135") (pin "136") (pinfunction "136_136") (pintype "passive"))
    )
    (net (code "142") (name "/PCIE0_TX1_N") (class "Default")
      (node (ref "J135") (pin "140") (pinfunction "140_140") (pintype "passive"))
    )
    (net (code "143") (name "/PCIE0_TX1_P") (class "Default")
      (node (ref "J135") (pin "142") (pinfunction "142_142") (pintype "passive"))
    )
    (net (code "144") (name "/PCIE0_TX2_N") (class "Default")
      (node (ref "J135") (pin "148") (pinfunction "148_148") (pintype "passive"))
    )
    (net (code "145") (name "/PCIE0_TX2_P") (class "Default")
      (node (ref "J135") (pin "150") (pinfunction "150_150") (pintype "passive"))
    )
    (net (code "146") (name "/PCIE0_TX3_N") (class "Default")
      (node (ref "J135") (pin "154") (pinfunction "154_154") (pintype "passive"))
    )
    (net (code "147") (name "/PCIE0_TX3_P") (class "Default")
      (node (ref "J135") (pin "156") (pinfunction "156_156") (pintype "passive"))
    )
    (net (code "148") (name "/PCIE0_WAKE") (class "Default")
      (node (ref "R228") (pin "1") (pinfunction "1_1") (pintype "passive"))
    )
    (net (code "149") (name "/PCIE1_CLKREQ") (class "Default")
      (node (ref "R224") (pin "1") (pinfunction "1_1") (pintype "passive"))
    )
    (net (code "150") (name "/PCIE1_CLK_N") (class "Default")
      (node (ref "J135") (pin "173") (pinfunction "173_173") (pintype "passive"))
    )
    (net (code "151") (name "/PCIE1_CLK_P") (class "Default")
      (node (ref "J135") (pin "175") (pinfunction "175_175") (pintype "passive"))
    )
    (net (code "152") (name "/PCIE1_RST") (class "Default")
      (node (ref "R225") (pin "1") (pinfunction "1_1") (pintype "passive"))
    )
    (net (code "153") (name "/PCIE1_RX0_N") (class "Default")
      (node (ref "J135") (pin "167") (pinfunction "167_167") (pintype "passive"))
    )
    (net (code "154") (name "/PCIE1_RX0_P") (class "Default")
      (node (ref "J135") (pin "169") (pinfunction "169_169") (pintype "passive"))
    )
    (net (code "155") (name "/PCIE1_TX0_N") (class "Default")
      (node (ref "J135") (pin "172") (pinfunction "172_172") (pintype "passive"))
    )
    (net (code "156") (name "/PCIE1_TX0_P") (class "Default")
      (node (ref "J135") (pin "174") (pinfunction "174_174") (pintype "passive"))
    )
    (net (code "157") (name "/PCIE2_CLK_N") (class "Default")
      (node (ref "J135") (pin "52") (pinfunction "52_52") (pintype "passive+no_connect"))
    )
    (net (code "158") (name "/PCIE2_CLK_P") (class "Default")
      (node (ref "J135") (pin "54") (pinfunction "54_54") (pintype "passive+no_connect"))
    )
    (net (code "159") (name "/PCIE2_RX0_N") (class "Default")
      (node (ref "J135") (pin "40") (pinfunction "40_40") (pintype "passive+no_connect"))
    )
    (net (code "160") (name "/PCIE2_RX0_P") (class "Default")
      (node (ref "J135") (pin "42") (pinfunction "42_42") (pintype "passive+no_connect"))
    )
    (net (code "161") (name "/PCIE2_RX1_N") (class "Default")
      (node (ref "J135") (pin "58") (pinfunction "58_58") (pintype "passive+no_connect"))
    )
    (net (code "162") (name "/PCIE2_RX1_P") (class "Default")
      (node (ref "J135") (pin "60") (pinfunction "60_60") (pintype "passive+no_connect"))
    )
    (net (code "163") (name "/PCIE2_TX0_N") (class "Default")
      (node (ref "J135") (pin "46") (pinfunction "46_46") (pintype "passive+no_connect"))
    )
    (net (code "164") (name "/PCIE2_TX0_P") (class "Default")
      (node (ref "J135") (pin "48") (pinfunction "48_48") (pintype "passive+no_connect"))
    )
    (net (code "165") (name "/PCIE2_TX1_N") (class "Default")
      (node (ref "J135") (pin "64") (pinfunction "64_64") (pintype "passive+no_connect"))
    )
    (net (code "166") (name "/PCIE2_TX1_P") (class "Default")
      (node (ref "J135") (pin "66") (pinfunction "66_66") (pintype "passive+no_connect"))
    )
    (net (code "167") (name "/PCIE3_CLK_N") (class "Default")
      (node (ref "J135") (pin "227") (pinfunction "227_227") (pintype "passive+no_connect"))
    )
    (net (code "168") (name "/PCIE3_CLK_P") (class "Default")
      (node (ref "J135") (pin "229") (pinfunction "229_229") (pintype "passive+no_connect"))
    )
    (net (code "169") (name "/PRE_USBSS1_RX_N") (class "Default")
      (node (ref "C231") (pin "2") (pinfunction "2_2") (pintype "passive"))
      (node (ref "J135") (pin "39") (pinfunction "39_39") (pintype "passive"))
    )
    (net (code "170") (name "/PRE_USBSS1_RX_P") (class "Default")
      (node (ref "C232") (pin "2") (pinfunction "2_2") (pintype "passive"))
      (node (ref "J135") (pin "41") (pinfunction "41_41") (pintype "passive"))
    )
    (net (code "171") (name "/USB2_0_N") (class "Default")
      (node (ref "J135") (pin "109") (pinfunction "109_109") (pintype "passive"))
    )
    (net (code "172") (name "/USB2_0_P") (class "Default")
      (node (ref "J135") (pin "111") (pinfunction "111_111") (pintype "passive"))
    )
    (net (code "173") (name "/USB2_1_N") (class "Default")
      (node (ref "J135") (pin "115") (pinfunction "115_115") (pintype "passive"))
    )
    (net (code "174") (name "/USB2_1_P") (class "Default")
      (node (ref "J135") (pin "117") (pinfunction "117_117") (pintype "passive"))
    )
    (net (code "175") (name "/USB2_2_N") (class "Default")
      (node (ref "J135") (pin "121") (pinfunction "121_121") (pintype "passive"))
    )
    (net (code "176") (name "/USB2_2_P") (class "Default")
      (node (ref "J135") (pin "123") (pinfunction "123_123") (pintype "passive"))
    )
    (net (code "177") (name "/USBSS0_RX_N") (class "Default")
      (node (ref "J135") (pin "161") (pinfunction "161_161") (pintype "passive+no_connect"))
    )
    (net (code "178") (name "/USBSS0_RX_P") (class "Default")
      (node (ref "J135") (pin "163") (pinfunction "163_163") (pintype "passive+no_connect"))
    )
    (net (code "179") (name "/USBSS0_TX_N") (class "Default")
      (node (ref "J135") (pin "166") (pinfunction "166_166") (pintype "passive+no_connect"))
    )
    (net (code "180") (name "/USBSS0_TX_P") (class "Default")
      (node (ref "J135") (pin "168") (pinfunction "168_168") (pintype "passive+no_connect"))
    )
    (net (code "181") (name "/USBSS1_RX_N") (class "Default")
      (node (ref "C231") (pin "1") (pinfunction "1_1") (pintype "passive"))
    )
    (net (code "182") (name "/USBSS1_RX_P") (class "Default")
      (node (ref "C232") (pin "1") (pinfunction "1_1") (pintype "passive"))
    )
    (net (code "183") (name "/USBSS1_TX_N") (class "Default")
      (node (ref "J135") (pin "45") (pinfunction "45_45") (pintype "passive"))
    )
    (net (code "184") (name "/USBSS1_TX_P") (class "Default")
      (node (ref "J135") (pin "47") (pinfunction "47_47") (pintype "passive"))
    )
    (net (code "185") (name "/USBSS2_RX_N") (class "Default")
      (node (ref "J135") (pin "51") (pinfunction "51_51") (pintype "passive+no_connect"))
    )
    (net (code "186") (name "/USBSS2_RX_P") (class "Default")
      (node (ref "J135") (pin "53") (pinfunction "53_53") (pintype "passive+no_connect"))
    )
    (net (code "187") (name "/USBSS2_TX_N") (class "Default")
      (node (ref "J135") (pin "57") (pinfunction "57_57") (pintype "passive+no_connect"))
    )
    (net (code "188") (name "/USBSS2_TX_P") (class "Default")
      (node (ref "J135") (pin "59") (pinfunction "59_59") (pintype "passive+no_connect"))
    )
    (net (code "189") (name "2V_AUX") (class "Default")
      (node (ref "C233") (pin "1") (pinfunction "1_1") (pintype "passive"))
      (node (ref "U26") (pin "3") (pinfunction "VIN_3") (pintype "power_in"))
    )
    (net (code "190") (name "3V3_AUX") (class "Default")
      (node (ref "R220") (pin "2") (pinfunction "2_2") (pintype "passive"))
      (node (ref "R221") (pin "2") (pinfunction "2_2") (pintype "passive"))
      (node (ref "R222") (pin "2") (pinfunction "2_2") (pintype "passive"))
      (node (ref "R223") (pin "2") (pinfunction "2_2") (pintype "passive"))
      (node (ref "R224") (pin "2") (pinfunction "2_2") (pintype "passive"))
      (node (ref "R225") (pin "2") (pinfunction "2_2") (pintype "passive"))
      (node (ref "R226") (pin "2") (pinfunction "2_2") (pintype "passive"))
      (node (ref "R227") (pin "2") (pinfunction "2_2") (pintype "passive"))
      (node (ref "R228") (pin "2") (pinfunction "2_2") (pintype "passive"))
      (node (ref "R229") (pin "2") (pinfunction "2_2") (pintype "passive"))
      (node (ref "R230") (pin "2") (pinfunction "2_2") (pintype "passive"))
      (node (ref "R235") (pin "2") (pinfunction "2_2") (pintype "passive"))
      (node (ref "R236") (pin "2") (pinfunction "2_2") (pintype "passive"))
    )
    (net (code "191") (name "3V3_INT") (class "Default")
      (node (ref "R232") (pin "2") (pinfunction "2_2") (pintype "passive"))
      (node (ref "R234") (pin "2") (pinfunction "2_2") (pintype "passive"))
      (node (ref "R238") (pin "2") (pinfunction "2_2") (pintype "passive"))
      (node (ref "R240") (pin "2") (pinfunction "2_2") (pintype "passive"))
    )
    (net (code "192") (name "3V3_M2_WIFI") (class "Default")
      (node (ref "R242") (pin "2") (pinfunction "2_2") (pintype "passive"))
      (node (ref "R244") (pin "2") (pinfunction "2_2") (pintype "passive"))
    )
    (net (code "193") (name "GND") (class "Default")
      (node (ref "BT1") (pin "3") (pinfunction "-_3") (pintype "passive"))
      (node (ref "C233") (pin "2") (pinfunction "2_2") (pintype "passive"))
      (node (ref "C234") (pin "2") (pinfunction "2_2") (pintype "passive"))
      (node (ref "C235") (pin "1") (pinfunction "C_1") (pintype "passive"))
      (node (ref "C236") (pin "1") (pinfunction "C_1") (pintype "passive"))
      (node (ref "C237") (pin "2") (pinfunction "2_2") (pintype "passive"))
      (node (ref "C238") (pin "2") (pinfunction "2_2") (pintype "passive"))
      (node (ref "C239") (pin "2") (pinfunction "2_2") (pintype "passive"))
      (node (ref "C240") (pin "2") (pinfunction "2_2") (pintype "passive"))
      (node (ref "C258") (pin "2") (pinfunction "2_2") (pintype "passive"))
      (node (ref "J135") (pin "1") (pinfunction "1_1") (pintype "passive"))
      (node (ref "J135") (pin "102") (pinfunction "102_102") (pintype "passive"))
      (node (ref "J135") (pin "107") (pinfunction "107_107") (pintype "passive"))
      (node (ref "J135") (pin "113") (pinfunction "113_113") (pintype "passive"))
      (node (ref "J135") (pin "119") (pinfunction "119_119") (pintype "passive"))
      (node (ref "J135") (pin "125") (pinfunction "125_125") (pintype "passive"))
      (node (ref "J135") (pin "129") (pinfunction "129_129") (pintype "passive"))
      (node (ref "J135") (pin "13") (pinfunction "13_13") (pintype "passive"))
      (node (ref "J135") (pin "132") (pinfunction "132_132") (pintype "passive"))
      (node (ref "J135") (pin "135") (pinfunction "135_135") (pintype "passive"))
      (node (ref "J135") (pin "138") (pinfunction "138_138") (pintype "passive"))
      (node (ref "J135") (pin "14") (pinfunction "14_14") (pintype "passive"))
      (node (ref "J135") (pin "141") (pinfunction "141_141") (pintype "passive"))
      (node (ref "J135") (pin "144") (pinfunction "144_144") (pintype "passive"))
      (node (ref "J135") (pin "146") (pinfunction "146_146") (pintype "passive"))
      (node (ref "J135") (pin "147") (pinfunction "147_147") (pintype "passive"))
      (node (ref "J135") (pin "152") (pinfunction "152_152") (pintype "passive"))
      (node (ref "J135") (pin "153") (pinfunction "153_153") (pintype "passive"))
      (node (ref "J135") (pin "158") (pinfunction "158_158") (pintype "passive"))
      (node (ref "J135") (pin "159") (pinfunction "159_159") (pintype "passive"))
      (node (ref "J135") (pin "164") (pinfunction "164_164") (pintype "passive"))
      (node (ref "J135") (pin "165") (pinfunction "165_165") (pintype "passive"))
      (node (ref "J135") (pin "170") (pinfunction "170_170") (pintype "passive"))
      (node (ref "J135") (pin "171") (pinfunction "171_171") (pintype "passive"))
      (node (ref "J135") (pin "176") (pinfunction "176_176") (pintype "passive"))
      (node (ref "J135") (pin "177") (pinfunction "177_177") (pintype "passive"))
      (node (ref "J135") (pin "19") (pinfunction "19_19") (pintype "passive"))
      (node (ref "J135") (pin "2") (pinfunction "2_2") (pintype "passive"))
      (node (ref "J135") (pin "20") (pinfunction "20_20") (pintype "passive"))
      (node (ref "J135") (pin "200") (pinfunction "200_200") (pintype "passive"))
      (node (ref "J135") (pin "201") (pinfunction "201_201") (pintype "passive"))
      (node (ref "J135") (pin "231") (pinfunction "231_231") (pintype "passive"))
      (node (ref "J135") (pin "241") (pinfunction "241_241") (pintype "passive"))
      (node (ref "J135") (pin "242") (pinfunction "242_242") (pintype "passive"))
      (node (ref "J135") (pin "243") (pinfunction "243_243") (pintype "passive"))
      (node (ref "J135") (pin "244") (pinfunction "244_244") (pintype "passive"))
      (node (ref "J135") (pin "245") (pinfunction "245_245") (pintype "passive"))
      (node (ref "J135") (pin "246") (pinfunction "246_246") (pintype "passive"))
      (node (ref "J135") (pin "247") (pinfunction "247_247") (pintype "passive"))
      (node (ref "J135") (pin "248") (pinfunction "248_248") (pintype "passive"))
      (node (ref "J135") (pin "249") (pinfunction "249_249") (pintype "passive"))
      (node (ref "J135") (pin "25") (pinfunction "25_25") (pintype "passive"))
      (node (ref "J135") (pin "250") (pinfunction "250_250") (pintype "passive"))
      (node (ref "J135") (pin "26") (pinfunction "26_26") (pintype "passive"))
      (node (ref "J135") (pin "261") (pinfunction "MNT_1_261") (pintype "passive"))
      (node (ref "J135") (pin "262") (pinfunction "MNT_2_262") (pintype "passive"))
      (node (ref "J135") (pin "31") (pinfunction "31_31") (pintype "passive"))
      (node (ref "J135") (pin "32") (pinfunction "32_32") (pintype "passive"))
      (node (ref "J135") (pin "37") (pinfunction "37_37") (pintype "passive"))
      (node (ref "J135") (pin "38") (pinfunction "38_38") (pintype "passive"))
      (node (ref "J135") (pin "43") (pinfunction "43_43") (pintype "passive"))
      (node (ref "J135") (pin "44") (pinfunction "44_44") (pintype "passive"))
      (node (ref "J135") (pin "49") (pinfunction "49_49") (pintype "passive"))
      (node (ref "J135") (pin "50") (pinfunction "50_50") (pintype "passive"))
      (node (ref "J135") (pin "55") (pinfunction "55_55") (pintype "passive"))
      (node (ref "J135") (pin "56") (pinfunction "56_56") (pintype "passive"))
      (node (ref "J135") (pin "61") (pinfunction "61_61") (pintype "passive"))
      (node (ref "J135") (pin "62") (pinfunction "62_62") (pintype "passive"))
      (node (ref "J135") (pin "67") (pinfunction "67_67") (pintype "passive"))
      (node (ref "J135") (pin "68") (pinfunction "68_68") (pintype "passive"))
      (node (ref "J135") (pin "7") (pinfunction "7_7") (pintype "passive"))
      (node (ref "J135") (pin "73") (pinfunction "73_73") (pintype "passive"))
      (node (ref "J135") (pin "74") (pinfunction "74_74") (pintype "passive"))
      (node (ref "J135") (pin "79") (pinfunction "79_79") (pintype "passive"))
      (node (ref "J135") (pin "8") (pinfunction "8_8") (pintype "passive"))
      (node (ref "J135") (pin "80") (pinfunction "80_80") (pintype "passive"))
      (node (ref "J135") (pin "85") (pinfunction "85_85") (pintype "passive"))
      (node (ref "J135") (pin "86") (pinfunction "86_86") (pintype "passive"))
      (node (ref "MP3") (pin "1") (pinfunction "1_1") (pintype "passive"))
      (node (ref "MP4") (pin "1") (pinfunction "1_1") (pintype "passive"))
      (node (ref "U26") (pin "1") (pinfunction "GND_1") (pintype "power_in"))
      (node (ref "U27") (pin "1") (pinfunction "~{OE}_1") (pintype "input"))
      (node (ref "U27") (pin "3") (pinfunction "GND_3") (pintype "power_in"))
    )
    (net (code "194") (name "JETSON_VCC") (class "Default")
      (node (ref "C235") (pin "2") (pinfunction "A_2") (pintype "passive"))
      (node (ref "C236") (pin "2") (pinfunction "A_2") (pintype "passive"))
      (node (ref "C237") (pin "1") (pinfunction "1_1") (pintype "passive"))
      (node (ref "C238") (pin "1") (pinfunction "1_1") (pintype "passive"))
      (node (ref "C239") (pin "1") (pinfunction "1_1") (pintype "passive"))
      (node (ref "C240") (pin "1") (pinfunction "1_1") (pintype "passive"))
      (node (ref "J135") (pin "251") (pinfunction "251_251") (pintype "passive"))
      (node (ref "J135") (pin "252") (pinfunction "252_252") (pintype "passive"))
      (node (ref "J135") (pin "253") (pinfunction "253_253") (pintype "passive"))
      (node (ref "J135") (pin "254") (pinfunction "254_254") (pintype "passive"))
      (node (ref "J135") (pin "255") (pinfunction "255_255") (pintype "passive"))
      (node (ref "J135") (pin "256") (pinfunction "256_256") (pintype "passive"))
      (node (ref "J135") (pin "257") (pinfunction "257_257") (pintype "passive"))
      (node (ref "J135") (pin "258") (pinfunction "258_258") (pintype "passive"))
      (node (ref "J135") (pin "259") (pinfunction "259_259") (pintype "passive"))
      (node (ref "J135") (pin "260") (pinfunction "260_260") (pintype "passive"))
      (node (ref "R241") (pin "2") (pinfunction "2_2") (pintype "passive"))
    )
    (net (code "195") (name "JSN_1V8_REF") (class "Default")
      (node (ref "C234") (pin "1") (pinfunction "1_1") (pintype "passive"))
      (node (ref "C258") (pin "1") (pinfunction "1_1") (pintype "passive"))
      (node (ref "Q32") (pin "2") (pinfunction "Gate1_2") (pintype "passive"))
      (node (ref "Q32") (pin "5") (pinfunction "Gate2_5") (pintype "passive"))
      (node (ref "Q33") (pin "2") (pinfunction "Gate1_2") (pintype "passive"))
      (node (ref "Q33") (pin "5") (pinfunction "Gate2_5") (pintype "passive"))
      (node (ref "R231") (pin "2") (pinfunction "2_2") (pintype "passive"))
      (node (ref "R233") (pin "2") (pinfunction "2_2") (pintype "passive"))
      (node (ref "R237") (pin "2") (pinfunction "2_2") (pintype "passive"))
      (node (ref "R239") (pin "2") (pinfunction "2_2") (pintype "passive"))
      (node (ref "R243") (pin "2") (pinfunction "2_2") (pintype "passive"))
      (node (ref "U26") (pin "2") (pinfunction "VOUT_2") (pintype "power_in"))
      (node (ref "U26") (pin "4") (pinfunction "VOUT_4") (pintype "power_in"))
      (node (ref "U27") (pin "5") (pinfunction "VCC_5") (pintype "power_in"))
    )
    (net (code "196") (name "Net-(D30-A)") (class "Default")
      (node (ref "BT1") (pin "1") (pinfunction "+_1") (pintype "passive"))
      (node (ref "BT1") (pin "2") (pinfunction "+_2") (pintype "passive"))
      (node (ref "D30") (pin "2") (pinfunction "A_2") (pintype "passive"))
    )
    (net (code "197") (name "unconnected-(J135-Pad70)") (class "Default")
      (node (ref "J135") (pin "70") (pinfunction "70_70") (pintype "passive+no_connect"))
    )
    (net (code "198") (name "unconnected-(J135-Pad72)") (class "Default")
      (node (ref "J135") (pin "72") (pinfunction "72_72") (pintype "passive+no_connect"))
    )
    (net (code "199") (name "unconnected-(J135-Pad76)") (class "Default")
      (node (ref "J135") (pin "76") (pinfunction "76_76") (pintype "passive+no_connect"))
    )
    (net (code "200") (name "unconnected-(J135-Pad78)") (class "Default")
      (node (ref "J135") (pin "78") (pinfunction "78_78") (pintype "passive+no_connect"))
    )
    (net (code "201") (name "unconnected-(J135-Pad82)") (class "Default")
      (node (ref "J135") (pin "82") (pinfunction "82_82") (pintype "passive+no_connect"))
    )
    (net (code "202") (name "unconnected-(J135-Pad84)") (class "Default")
      (node (ref "J135") (pin "84") (pinfunction "84_84") (pintype "passive+no_connect"))
    )
    (net (code "203") (name "unconnected-(J135-Pad88)") (class "Default")
      (node (ref "J135") (pin "88") (pinfunction "88_88") (pintype "passive+no_connect"))
    )
    (net (code "204") (name "unconnected-(J135-Pad90)") (class "Default")
      (node (ref "J135") (pin "90") (pinfunction "90_90") (pintype "passive+no_connect"))
    )
    (net (code "205") (name "unconnected-(J135-Pad92)") (class "Default")
      (node (ref "J135") (pin "92") (pinfunction "92_92") (pintype "passive+no_connect"))
    )
  )
)
